# Encoder.net
KiCad netlist of a schematic drawn in Altium Designer
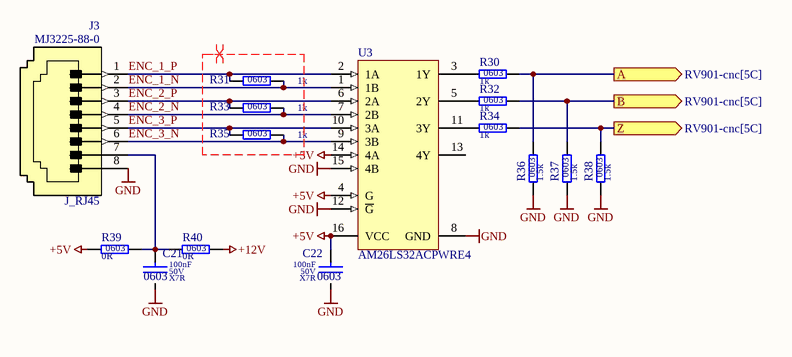
[diagram p0: Encoder.SchDoc]

(export (version "E")
  (design (tool "Eeschema 10.0.6"))
  (components
    (comp (ref "C21")
      (value "100nF")
      (footprint "C_0603_1608")
      (description "Capacitor")
      (fields
        (field (name "DIELECTRIC") "X7R")
        (field (name "VOLTAGE") "50V")
        (field (name "SCH_FOOTPRINT") "0603")
        (field (name "PART NUMBER") "C_100nF_50V_X7R_0603_5")
        (field (name "MANUFACTURER") "Samsung")
      )
      (libsource (lib "Library") (part "C"))
    )
    (comp (ref "C22")
      (value "100nF")
      (footprint "C_0603_1608")
      (description "Capacitor")
      (fields
        (field (name "DIELECTRIC") "X7R")
        (field (name "VOLTAGE") "50V")
        (field (name "SCH_FOOTPRINT") "0603")
        (field (name "PART NUMBER") "C_100nF_50V_X7R_0603_5")
        (field (name "MANUFACTURER") "Samsung")
      )
      (libsource (lib "Library") (part "C"))
    )
    (comp (ref "J3")
      (value "MJ3225-88-0")
      (footprint "J_RJ45_MJ3225-88-0")
      (fields
        (field (name "SCH_FOOTPRINT") "J_RJ45")
        (field (name "PART NUMBER") "J_RJ45_MJ3225-88-0")
        (field (name "MANUFACTURER") "Global Connector Technology")
        (field (name "Comment") "Modular Connector, Modular Jack, 1 x 1 (Port), 8P8C, Cat3")
      )
      (libsource (lib "Library") (part "J_RJ45"))
    )
    (comp (ref "R30")
      (value "1k")
      (footprint "R_0603_1608")
      (fields
        (field (name "SCH_FOOTPRINT") "0603")
        (field (name "PART NUMBER") "R_1k_0603_1_AECQ0")
        (field (name "VOLTAGE") "75V")
        (field (name "POWER") "100mW")
      )
      (libsource (lib "Library") (part "R"))
    )
    (comp (ref "R31")
      (value "1k")
      (footprint "R_0603_1608")
      (fields
        (field (name "SCH_FOOTPRINT") "0603")
        (field (name "PART NUMBER") "R_1k_0603_1_AECQ0")
        (field (name "VOLTAGE") "75V")
        (field (name "POWER") "100mW")
      )
      (libsource (lib "Library") (part "R"))
    )
    (comp (ref "R32")
      (value "1k")
      (footprint "R_0603_1608")
      (fields
        (field (name "SCH_FOOTPRINT") "0603")
        (field (name "PART NUMBER") "R_1k_0603_1_AECQ0")
        (field (name "VOLTAGE") "75V")
        (field (name "POWER") "100mW")
      )
      (libsource (lib "Library") (part "R"))
    )
    (comp (ref "R33")
      (value "1k")
      (footprint "R_0603_1608")
      (fields
        (field (name "SCH_FOOTPRINT") "0603")
        (field (name "PART NUMBER") "R_1k_0603_1_AECQ0")
        (field (name "VOLTAGE") "75V")
        (field (name "POWER") "100mW")
      )
      (libsource (lib "Library") (part "R"))
    )
    (comp (ref "R34")
      (value "1k")
      (footprint "R_0603_1608")
      (fields
        (field (name "SCH_FOOTPRINT") "0603")
        (field (name "PART NUMBER") "R_1k_0603_1_AECQ0")
        (field (name "VOLTAGE") "75V")
        (field (name "POWER") "100mW")
      )
      (libsource (lib "Library") (part "R"))
    )
    (comp (ref "R35")
      (value "1k")
      (footprint "R_0603_1608")
      (fields
        (field (name "SCH_FOOTPRINT") "0603")
        (field (name "PART NUMBER") "R_1k_0603_1_AECQ0")
        (field (name "VOLTAGE") "75V")
        (field (name "POWER") "100mW")
      )
      (libsource (lib "Library") (part "R"))
    )
    (comp (ref "R36")
      (value "1.5k")
      (footprint "R_0603_1608")
      (fields
        (field (name "SCH_FOOTPRINT") "0603")
        (field (name "PART NUMBER") "R_1.5k_0603_1")
        (field (name "VOLTAGE") "50V")
        (field (name "POWER") "100mW")
      )
      (libsource (lib "Library") (part "R"))
    )
    (comp (ref "R37")
      (value "1.5k")
      (footprint "R_0603_1608")
      (fields
        (field (name "SCH_FOOTPRINT") "0603")
        (field (name "PART NUMBER") "R_1.5k_0603_1")
        (field (name "VOLTAGE") "50V")
        (field (name "POWER") "100mW")
      )
      (libsource (lib "Library") (part "R"))
    )
    (comp (ref "R38")
      (value "1.5k")
      (footprint "R_0603_1608")
      (fields
        (field (name "SCH_FOOTPRINT") "0603")
        (field (name "PART NUMBER") "R_1.5k_0603_1")
        (field (name "VOLTAGE") "50V")
        (field (name "POWER") "100mW")
      )
      (libsource (lib "Library") (part "R"))
    )
    (comp (ref "R39")
      (value "0R")
      (footprint "R_0603_1608")
      (fields
        (field (name "SCH_FOOTPRINT") "0603")
        (field (name "PART NUMBER") "R_0R_0603_1")
        (field (name "VOLTAGE") "75V")
        (field (name "POWER") "100mW")
      )
      (libsource (lib "Library") (part "R"))
    )
    (comp (ref "R40")
      (value "0R")
      (footprint "R_0603_1608")
      (fields
        (field (name "SCH_FOOTPRINT") "0603")
        (field (name "PART NUMBER") "R_0R_0603_1")
        (field (name "VOLTAGE") "75V")
        (field (name "POWER") "100mW")
      )
      (libsource (lib "Library") (part "R"))
    )
    (comp (ref "U3")
      (value "AM26LS32ACPWRE4")
      (footprint "PW16_L")
      (fields (field (name "MANUFACTURER") "Texas Instruments"))
      (libsource (lib "Altium Content Vault") (part "TI-AM26LS32AC-TSSOP_PW-16"))
    )
  )
  (nets
    (net (code "1") (name "+5V") (class "Default")
      (node (ref "C22") (pin "1") (pinfunction "1_1") (pintype "passive"))
      (node (ref "R39") (pin "1") (pinfunction "1_1") (pintype "passive"))
      (node (ref "U3") (pin "14") (pinfunction "4A_14") (pintype "input"))
      (node (ref "U3") (pin "16") (pinfunction "VCC_16") (pintype "power_in"))
      (node (ref "U3") (pin "4") (pinfunction "G_4") (pintype "input"))
    )
    (net (code "2") (name "+12V") (class "Default")
      (node (ref "R40") (pin "2") (pinfunction "2_2") (pintype "passive"))
    )
    (net (code "3") (name "/A") (class "Default")
      (node (ref "R30") (pin "2") (pinfunction "2_2") (pintype "passive"))
      (node (ref "R36") (pin "2") (pinfunction "2_2") (pintype "passive"))
    )
    (net (code "4") (name "/B") (class "Default")
      (node (ref "R32") (pin "2") (pinfunction "2_2") (pintype "passive"))
      (node (ref "R37") (pin "2") (pinfunction "2_2") (pintype "passive"))
    )
    (net (code "5") (name "/ENC_1_N") (class "Default")
      (node (ref "J3") (pin "2") (pintype "output"))
      (node (ref "R31") (pin "2") (pinfunction "2_2") (pintype "passive"))
      (node (ref "U3") (pin "1") (pinfunction "1B_1") (pintype "input"))
    )
    (net (code "6") (name "/ENC_1_P") (class "Default")
      (node (ref "J3") (pin "1") (pintype "output"))
      (node (ref "R31") (pin "1") (pinfunction "1_1") (pintype "passive"))
      (node (ref "U3") (pin "2") (pinfunction "1A_2") (pintype "input"))
    )
    (net (code "7") (name "/ENC_2_N") (class "Default")
      (node (ref "J3") (pin "4") (pintype "output"))
      (node (ref "R33") (pin "2") (pinfunction "2_2") (pintype "passive"))
      (node (ref "U3") (pin "7") (pinfunction "2B_7") (pintype "input"))
    )
    (net (code "8") (name "/ENC_2_P") (class "Default")
      (node (ref "J3") (pin "3") (pintype "output"))
      (node (ref "R33") (pin "1") (pinfunction "1_1") (pintype "passive"))
      (node (ref "U3") (pin "6") (pinfunction "2A_6") (pintype "input"))
    )
    (net (code "9") (name "/ENC_3_N") (class "Default")
      (node (ref "J3") (pin "6") (pintype "output"))
      (node (ref "R35") (pin "2") (pinfunction "2_2") (pintype "passive"))
      (node (ref "U3") (pin "9") (pinfunction "3B_9") (pintype "input"))
    )
    (net (code "10") (name "/ENC_3_P") (class "Default")
      (node (ref "J3") (pin "5") (pintype "output"))
      (node (ref "R35") (pin "1") (pinfunction "1_1") (pintype "passive"))
      (node (ref "U3") (pin "10") (pinfunction "3A_10") (pintype "input"))
    )
    (net (code "11") (name "/Z") (class "Default")
      (node (ref "R34") (pin "2") (pinfunction "2_2") (pintype "passive"))
      (node (ref "R38") (pin "2") (pinfunction "2_2") (pintype "passive"))
    )
    (net (code "12") (name "GND") (class "Default")
      (node (ref "C21") (pin "2") (pinfunction "2_2") (pintype "passive"))
      (node (ref "C22") (pin "2") (pinfunction "2_2") (pintype "passive"))
      (node (ref "J3") (pin "8") (pintype "passive"))
      (node (ref "R36") (pin "1") (pinfunction "1_1") (pintype "passive"))
      (node (ref "R37") (pin "1") (pinfunction "1_1") (pintype "passive"))
      (node (ref "R38") (pin "1") (pinfunction "1_1") (pintype "passive"))
      (node (ref "U3") (pin "12") (pinfunction "~{G}_12") (pintype "input"))
      (node (ref "U3") (pin "15") (pinfunction "4B_15") (pintype "input"))
      (node (ref "U3") (pin "8") (pinfunction "GND_8") (pintype "power_in"))
    )
    (net (code "13") (name "Net-(C21-Pad1)") (class "Default")
      (node (ref "C21") (pin "1") (pinfunction "1_1") (pintype "passive"))
      (node (ref "J3") (pin "7") (pintype "power_in"))
      (node (ref "R39") (pin "2") (pinfunction "2_2") (pintype "passive"))
      (node (ref "R40") (pin "1") (pinfunction "1_1") (pintype "passive"))
    )
    (net (code "14") (name "Net-(U3-1Y)") (class "Default")
      (node (ref "R30") (pin "1") (pinfunction "1_1") (pintype "passive"))
      (node (ref "U3") (pin "3") (pinfunction "1Y_3") (pintype "tri_state"))
    )
    (net (code "15") (name "Net-(U3-2Y)") (class "Default")
      (node (ref "R32") (pin "1") (pinfunction "1_1") (pintype "passive"))
      (node (ref "U3") (pin "5") (pinfunction "2Y_5") (pintype "tri_state"))
    )
    (net (code "16") (name "Net-(U3-3Y)") (class "Default")
      (node (ref "R34") (pin "1") (pinfunction "1_1") (pintype "passive"))
      (node (ref "U3") (pin "11") (pinfunction "3Y_11") (pintype "tri_state"))
    )
    (net (code "17") (name "unconnected-(U3-4Y-Pad13)") (class "Default")
      (node (ref "U3") (pin "13") (pinfunction "4Y_13") (pintype "tri_state"))
    )
  )
)
